# Sheet1.net
KiCad netlist of a schematic drawn in Altium Designer
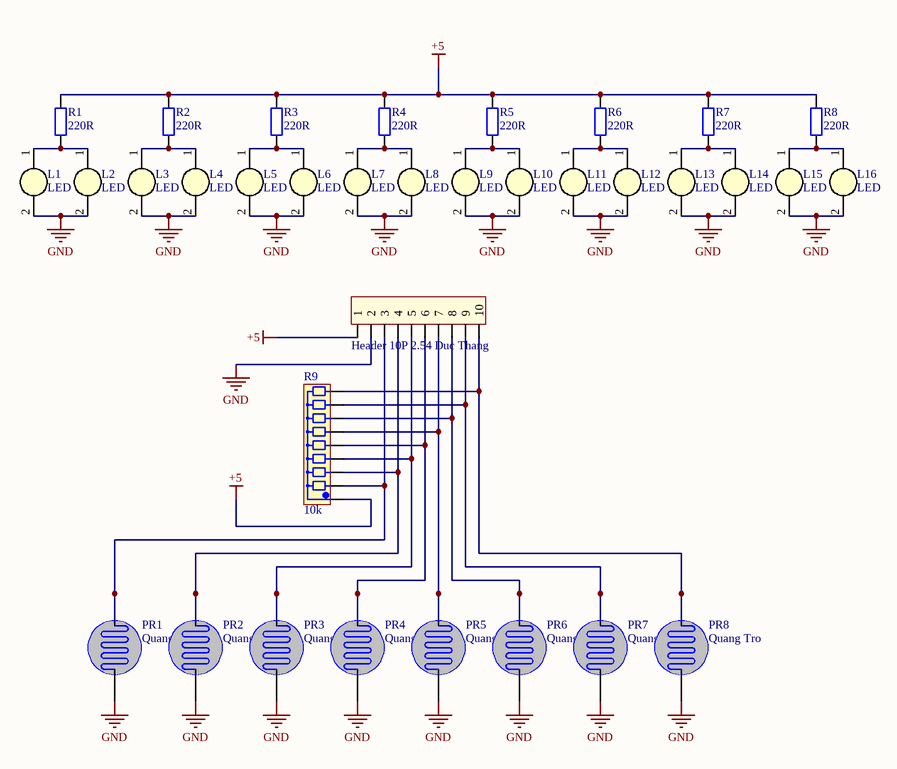
[diagram p0: Sheet1.SchDoc]

(export (version "E")
  (design (tool "Eeschema 10.0.6"))
  (components
    (comp (ref "H1")
      (value "Header 10P 2.54 Duc Thang")
      (footprint "XH2.54M-10")
      (description "Cắm")
      (libsource (lib "Header") (part "Header 10P 2.54 Duc Thang"))
    )
    (comp (ref "L1")
      (value "LED")
      (footprint "LED-5MM-WHITE")
      (description "Cắm")
      (libsource (lib "Led") (part "LED 5mm Trang"))
    )
    (comp (ref "L2")
      (value "LED")
      (footprint "LED-5MM-WHITE")
      (description "Cắm")
      (libsource (lib "Led") (part "LED 5mm Trang"))
    )
    (comp (ref "L3")
      (value "LED")
      (footprint "LED-5MM-WHITE")
      (description "Cắm")
      (libsource (lib "Led") (part "LED 5mm Trang"))
    )
    (comp (ref "L4")
      (value "LED")
      (footprint "LED-5MM-WHITE")
      (description "Cắm")
      (libsource (lib "Led") (part "LED 5mm Trang"))
    )
    (comp (ref "L5")
      (value "LED")
      (footprint "LED-5MM-WHITE")
      (description "Cắm")
      (libsource (lib "Led") (part "LED 5mm Trang"))
    )
    (comp (ref "L6")
      (value "LED")
      (footprint "LED-5MM-WHITE")
      (description "Cắm")
      (libsource (lib "Led") (part "LED 5mm Trang"))
    )
    (comp (ref "L7")
      (value "LED")
      (footprint "LED-5MM-WHITE")
      (description "Cắm")
      (libsource (lib "Led") (part "LED 5mm Trang"))
    )
    (comp (ref "L8")
      (value "LED")
      (footprint "LED-5MM-WHITE")
      (description "Cắm")
      (libsource (lib "Led") (part "LED 5mm Trang"))
    )
    (comp (ref "L9")
      (value "LED")
      (footprint "LED-5MM-WHITE")
      (description "Cắm")
      (libsource (lib "Led") (part "LED 5mm Trang"))
    )
    (comp (ref "L10")
      (value "LED")
      (footprint "LED-5MM-WHITE")
      (description "Cắm")
      (libsource (lib "Led") (part "LED 5mm Trang"))
    )
    (comp (ref "L11")
      (value "LED")
      (footprint "LED-5MM-WHITE")
      (description "Cắm")
      (libsource (lib "Led") (part "LED 5mm Trang"))
    )
    (comp (ref "L12")
      (value "LED")
      (footprint "LED-5MM-WHITE")
      (description "Cắm")
      (libsource (lib "Led") (part "LED 5mm Trang"))
    )
    (comp (ref "L13")
      (value "LED")
      (footprint "LED-5MM-WHITE")
      (description "Cắm")
      (libsource (lib "Led") (part "LED 5mm Trang"))
    )
    (comp (ref "L14")
      (value "LED")
      (footprint "LED-5MM-WHITE")
      (description "Cắm")
      (libsource (lib "Led") (part "LED 5mm Trang"))
    )
    (comp (ref "L15")
      (value "LED")
      (footprint "LED-5MM-WHITE")
      (description "Cắm")
      (libsource (lib "Led") (part "LED 5mm Trang"))
    )
    (comp (ref "L16")
      (value "LED")
      (footprint "LED-5MM-WHITE")
      (description "Cắm")
      (libsource (lib "Led") (part "LED 5mm Trang"))
    )
    (comp (ref "PR1")
      (value "Quang Tro")
      (footprint "Quang Tro")
      (description "Photoresistor")
      (fields (field (name "CREATOR") "Bien Nguyen"))
      (libsource (lib "Component") (part "Quang Tro"))
    )
    (comp (ref "PR2")
      (value "Quang Tro")
      (footprint "Quang Tro")
      (description "Photoresistor")
      (fields (field (name "CREATOR") "Bien Nguyen"))
      (libsource (lib "Component") (part "Quang Tro"))
    )
    (comp (ref "PR3")
      (value "Quang Tro")
      (footprint "Quang Tro")
      (description "Photoresistor")
      (fields (field (name "CREATOR") "Bien Nguyen"))
      (libsource (lib "Component") (part "Quang Tro"))
    )
    (comp (ref "PR4")
      (value "Quang Tro")
      (footprint "Quang Tro")
      (description "Photoresistor")
      (fields (field (name "CREATOR") "Bien Nguyen"))
      (libsource (lib "Component") (part "Quang Tro"))
    )
    (comp (ref "PR5")
      (value "Quang Tro")
      (footprint "Quang Tro")
      (description "Photoresistor")
      (fields (field (name "CREATOR") "Bien Nguyen"))
      (libsource (lib "Component") (part "Quang Tro"))
    )
    (comp (ref "PR6")
      (value "Quang Tro")
      (footprint "Quang Tro")
      (description "Photoresistor")
      (fields (field (name "CREATOR") "Bien Nguyen"))
      (libsource (lib "Component") (part "Quang Tro"))
    )
    (comp (ref "PR7")
      (value "Quang Tro")
      (footprint "Quang Tro")
      (description "Photoresistor")
      (fields (field (name "CREATOR") "Bien Nguyen"))
      (libsource (lib "Component") (part "Quang Tro"))
    )
    (comp (ref "PR8")
      (value "Quang Tro")
      (footprint "Quang Tro")
      (description "Photoresistor")
      (fields (field (name "CREATOR") "Bien Nguyen"))
      (libsource (lib "Component") (part "Quang Tro"))
    )
    (comp (ref "R1")
      (value "220R")
      (footprint "tro vach 1/4w")
      (description "Cắm")
      (libsource (lib "Resistor") (part "Tro Vach 1/4W 5% 220R"))
    )
    (comp (ref "R2")
      (value "220R")
      (footprint "tro vach 1/4w")
      (description "Cắm")
      (libsource (lib "Resistor") (part "Tro Vach 1/4W 5% 220R"))
    )
    (comp (ref "R3")
      (value "220R")
      (footprint "tro vach 1/4w")
      (description "Cắm")
      (libsource (lib "Resistor") (part "Tro Vach 1/4W 5% 220R"))
    )
    (comp (ref "R4")
      (value "220R")
      (footprint "tro vach 1/4w")
      (description "Cắm")
      (libsource (lib "Resistor") (part "Tro Vach 1/4W 5% 220R"))
    )
    (comp (ref "R5")
      (value "220R")
      (footprint "tro vach 1/4w")
      (description "Cắm")
      (libsource (lib "Resistor") (part "Tro Vach 1/4W 5% 220R"))
    )
    (comp (ref "R6")
      (value "220R")
      (footprint "tro vach 1/4w")
      (description "Cắm")
      (libsource (lib "Resistor") (part "Tro Vach 1/4W 5% 220R"))
    )
    (comp (ref "R7")
      (value "220R")
      (footprint "tro vach 1/4w")
      (description "Cắm")
      (libsource (lib "Resistor") (part "Tro Vach 1/4W 5% 220R"))
    )
    (comp (ref "R8")
      (value "220R")
      (footprint "tro vach 1/4w")
      (description "Cắm")
      (libsource (lib "Resistor") (part "Tro Vach 1/4W 5% 220R"))
    )
    (comp (ref "R9")
      (value "10k")
      (footprint "tro bang a9")
      (description "Cắm")
      (libsource (lib "Resistor") (part "Tro Bang A9 100k"))
    )
  )
  (nets
    (net (code "1") (name "+5") (class "Default")
      (node (ref "H1") (pin "1") (pinfunction "1_1") (pintype "passive"))
      (node (ref "R1") (pin "2") (pinfunction "2_2") (pintype "passive"))
      (node (ref "R2") (pin "2") (pinfunction "2_2") (pintype "passive"))
      (node (ref "R3") (pin "2") (pinfunction "2_2") (pintype "passive"))
      (node (ref "R4") (pin "2") (pinfunction "2_2") (pintype "passive"))
      (node (ref "R5") (pin "2") (pinfunction "2_2") (pintype "passive"))
      (node (ref "R6") (pin "2") (pinfunction "2_2") (pintype "passive"))
      (node (ref "R7") (pin "2") (pinfunction "2_2") (pintype "passive"))
      (node (ref "R8") (pin "2") (pinfunction "2_2") (pintype "passive"))
      (node (ref "R9") (pin "1") (pinfunction "1_1") (pintype "passive"))
    )
    (net (code "2") (name "GND") (class "Default")
      (node (ref "H1") (pin "2") (pinfunction "2_2") (pintype "passive"))
      (node (ref "L1") (pin "2") (pinfunction "K_2") (pintype "passive"))
      (node (ref "L10") (pin "2") (pinfunction "K_2") (pintype "passive"))
      (node (ref "L11") (pin "2") (pinfunction "K_2") (pintype "passive"))
      (node (ref "L12") (pin "2") (pinfunction "K_2") (pintype "passive"))
      (node (ref "L13") (pin "2") (pinfunction "K_2") (pintype "passive"))
      (node (ref "L14") (pin "2") (pinfunction "K_2") (pintype "passive"))
      (node (ref "L15") (pin "2") (pinfunction "K_2") (pintype "passive"))
      (node (ref "L16") (pin "2") (pinfunction "K_2") (pintype "passive"))
      (node (ref "L2") (pin "2") (pinfunction "K_2") (pintype "passive"))
      (node (ref "L3") (pin "2") (pinfunction "K_2") (pintype "passive"))
      (node (ref "L4") (pin "2") (pinfunction "K_2") (pintype "passive"))
      (node (ref "L5") (pin "2") (pinfunction "K_2") (pintype "passive"))
      (node (ref "L6") (pin "2") (pinfunction "K_2") (pintype "passive"))
      (node (ref "L7") (pin "2") (pinfunction "K_2") (pintype "passive"))
      (node (ref "L8") (pin "2") (pinfunction "K_2") (pintype "passive"))
      (node (ref "L9") (pin "2") (pinfunction "K_2") (pintype "passive"))
      (node (ref "PR1") (pin "1") (pinfunction "1_1") (pintype "passive"))
      (node (ref "PR2") (pin "1") (pinfunction "1_1") (pintype "passive"))
      (node (ref "PR3") (pin "1") (pinfunction "1_1") (pintype "passive"))
      (node (ref "PR4") (pin "1") (pinfunction "1_1") (pintype "passive"))
      (node (ref "PR5") (pin "1") (pinfunction "1_1") (pintype "passive"))
      (node (ref "PR6") (pin "1") (pinfunction "1_1") (pintype "passive"))
      (node (ref "PR7") (pin "1") (pinfunction "1_1") (pintype "passive"))
      (node (ref "PR8") (pin "1") (pinfunction "1_1") (pintype "passive"))
    )
    (net (code "3") (name "Net-(H1-Pad3)") (class "Default")
      (node (ref "H1") (pin "3") (pinfunction "3_3") (pintype "passive"))
      (node (ref "PR1") (pin "2") (pinfunction "2_2") (pintype "passive"))
      (node (ref "R9") (pin "2") (pinfunction "2_2") (pintype "passive"))
    )
    (net (code "4") (name "Net-(H1-Pad4)") (class "Default")
      (node (ref "H1") (pin "4") (pinfunction "4_4") (pintype "passive"))
      (node (ref "PR2") (pin "2") (pinfunction "2_2") (pintype "passive"))
      (node (ref "R9") (pin "3") (pinfunction "3_3") (pintype "passive"))
    )
    (net (code "5") (name "Net-(H1-Pad5)") (class "Default")
      (node (ref "H1") (pin "5") (pinfunction "5_5") (pintype "passive"))
      (node (ref "PR3") (pin "2") (pinfunction "2_2") (pintype "passive"))
      (node (ref "R9") (pin "4") (pinfunction "4_4") (pintype "passive"))
    )
    (net (code "6") (name "Net-(H1-Pad6)") (class "Default")
      (node (ref "H1") (pin "6") (pinfunction "6_6") (pintype "passive"))
      (node (ref "PR4") (pin "2") (pinfunction "2_2") (pintype "passive"))
      (node (ref "R9") (pin "5") (pinfunction "5_5") (pintype "passive"))
    )
    (net (code "7") (name "Net-(H1-Pad7)") (class "Default")
      (node (ref "H1") (pin "7") (pinfunction "7_7") (pintype "passive"))
      (node (ref "PR5") (pin "2") (pinfunction "2_2") (pintype "passive"))
      (node (ref "R9") (pin "6") (pinfunction "6_6") (pintype "passive"))
    )
    (net (code "8") (name "Net-(H1-Pad8)") (class "Default")
      (node (ref "H1") (pin "8") (pinfunction "8_8") (pintype "passive"))
      (node (ref "PR6") (pin "2") (pinfunction "2_2") (pintype "passive"))
      (node (ref "R9") (pin "7") (pinfunction "7_7") (pintype "passive"))
    )
    (net (code "9") (name "Net-(H1-Pad9)") (class "Default")
      (node (ref "H1") (pin "9") (pinfunction "9_9") (pintype "passive"))
      (node (ref "PR7") (pin "2") (pinfunction "2_2") (pintype "passive"))
      (node (ref "R9") (pin "8") (pinfunction "8_8") (pintype "passive"))
    )
    (net (code "10") (name "Net-(H1-Pad10)") (class "Default")
      (node (ref "H1") (pin "10") (pinfunction "10_10") (pintype "passive"))
      (node (ref "PR8") (pin "2") (pinfunction "2_2") (pintype "passive"))
      (node (ref "R9") (pin "9") (pinfunction "9_9") (pintype "passive"))
    )
    (net (code "11") (name "Net-(L1-A)") (class "Default")
      (node (ref "L1") (pin "1") (pinfunction "A_1") (pintype "passive"))
      (node (ref "L2") (pin "1") (pinfunction "A_1") (pintype "passive"))
      (node (ref "R1") (pin "1") (pinfunction "1_1") (pintype "passive"))
    )
    (net (code "12") (name "Net-(L3-A)") (class "Default")
      (node (ref "L3") (pin "1") (pinfunction "A_1") (pintype "passive"))
      (node (ref "L4") (pin "1") (pinfunction "A_1") (pintype "passive"))
      (node (ref "R2") (pin "1") (pinfunction "1_1") (pintype "passive"))
    )
    (net (code "13") (name "Net-(L5-A)") (class "Default")
      (node (ref "L5") (pin "1") (pinfunction "A_1") (pintype "passive"))
      (node (ref "L6") (pin "1") (pinfunction "A_1") (pintype "passive"))
      (node (ref "R3") (pin "1") (pinfunction "1_1") (pintype "passive"))
    )
    (net (code "14") (name "Net-(L7-A)") (class "Default")
      (node (ref "L7") (pin "1") (pinfunction "A_1") (pintype "passive"))
      (node (ref "L8") (pin "1") (pinfunction "A_1") (pintype "passive"))
      (node (ref "R4") (pin "1") (pinfunction "1_1") (pintype "passive"))
    )
    (net (code "15") (name "Net-(L10-A)") (class "Default")
      (node (ref "L10") (pin "1") (pinfunction "A_1") (pintype "passive"))
      (node (ref "L9") (pin "1") (pinfunction "A_1") (pintype "passive"))
      (node (ref "R5") (pin "1") (pinfunction "1_1") (pintype "passive"))
    )
    (net (code "16") (name "Net-(L11-A)") (class "Default")
      (node (ref "L11") (pin "1") (pinfunction "A_1") (pintype "passive"))
      (node (ref "L12") (pin "1") (pinfunction "A_1") (pintype "passive"))
      (node (ref "R6") (pin "1") (pinfunction "1_1") (pintype "passive"))
    )
    (net (code "17") (name "Net-(L13-A)") (class "Default")
      (node (ref "L13") (pin "1") (pinfunction "A_1") (pintype "passive"))
      (node (ref "L14") (pin "1") (pinfunction "A_1") (pintype "passive"))
      (node (ref "R7") (pin "1") (pinfunction "1_1") (pintype "passive"))
    )
    (net (code "18") (name "Net-(L15-A)") (class "Default")
      (node (ref "L15") (pin "1") (pinfunction "A_1") (pintype "passive"))
      (node (ref "L16") (pin "1") (pinfunction "A_1") (pintype "passive"))
      (node (ref "R8") (pin "1") (pinfunction "1_1") (pintype "passive"))
    )
  )
)
